# CI_V.net
KiCad netlist of a schematic drawn in EAGLE
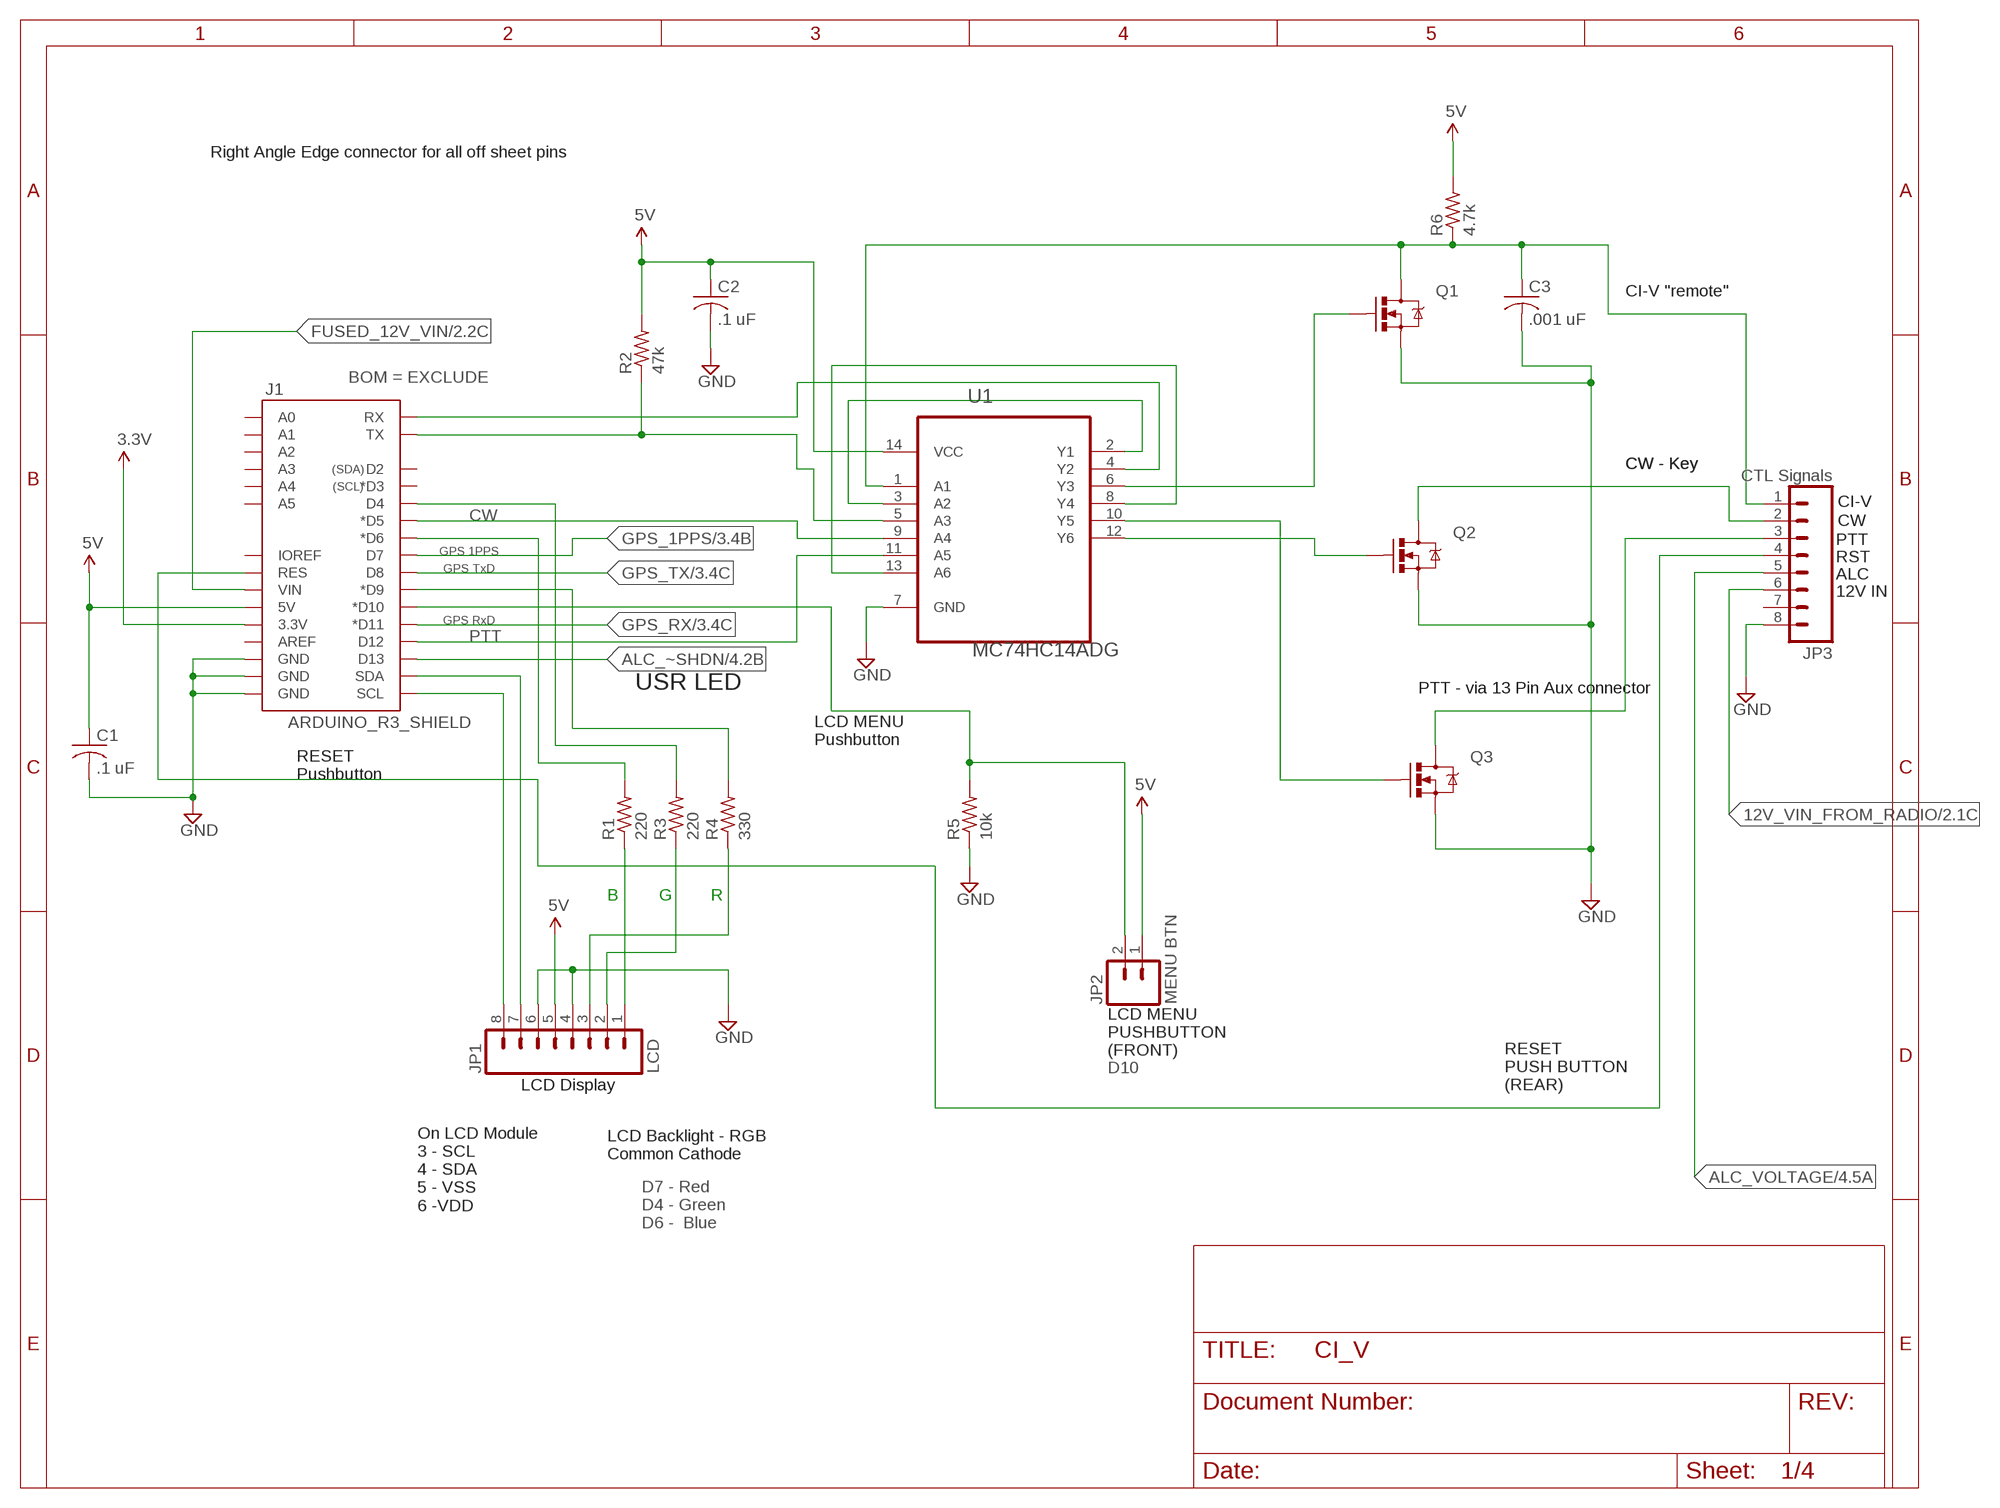
[diagram p0: schematic, sheet 1]
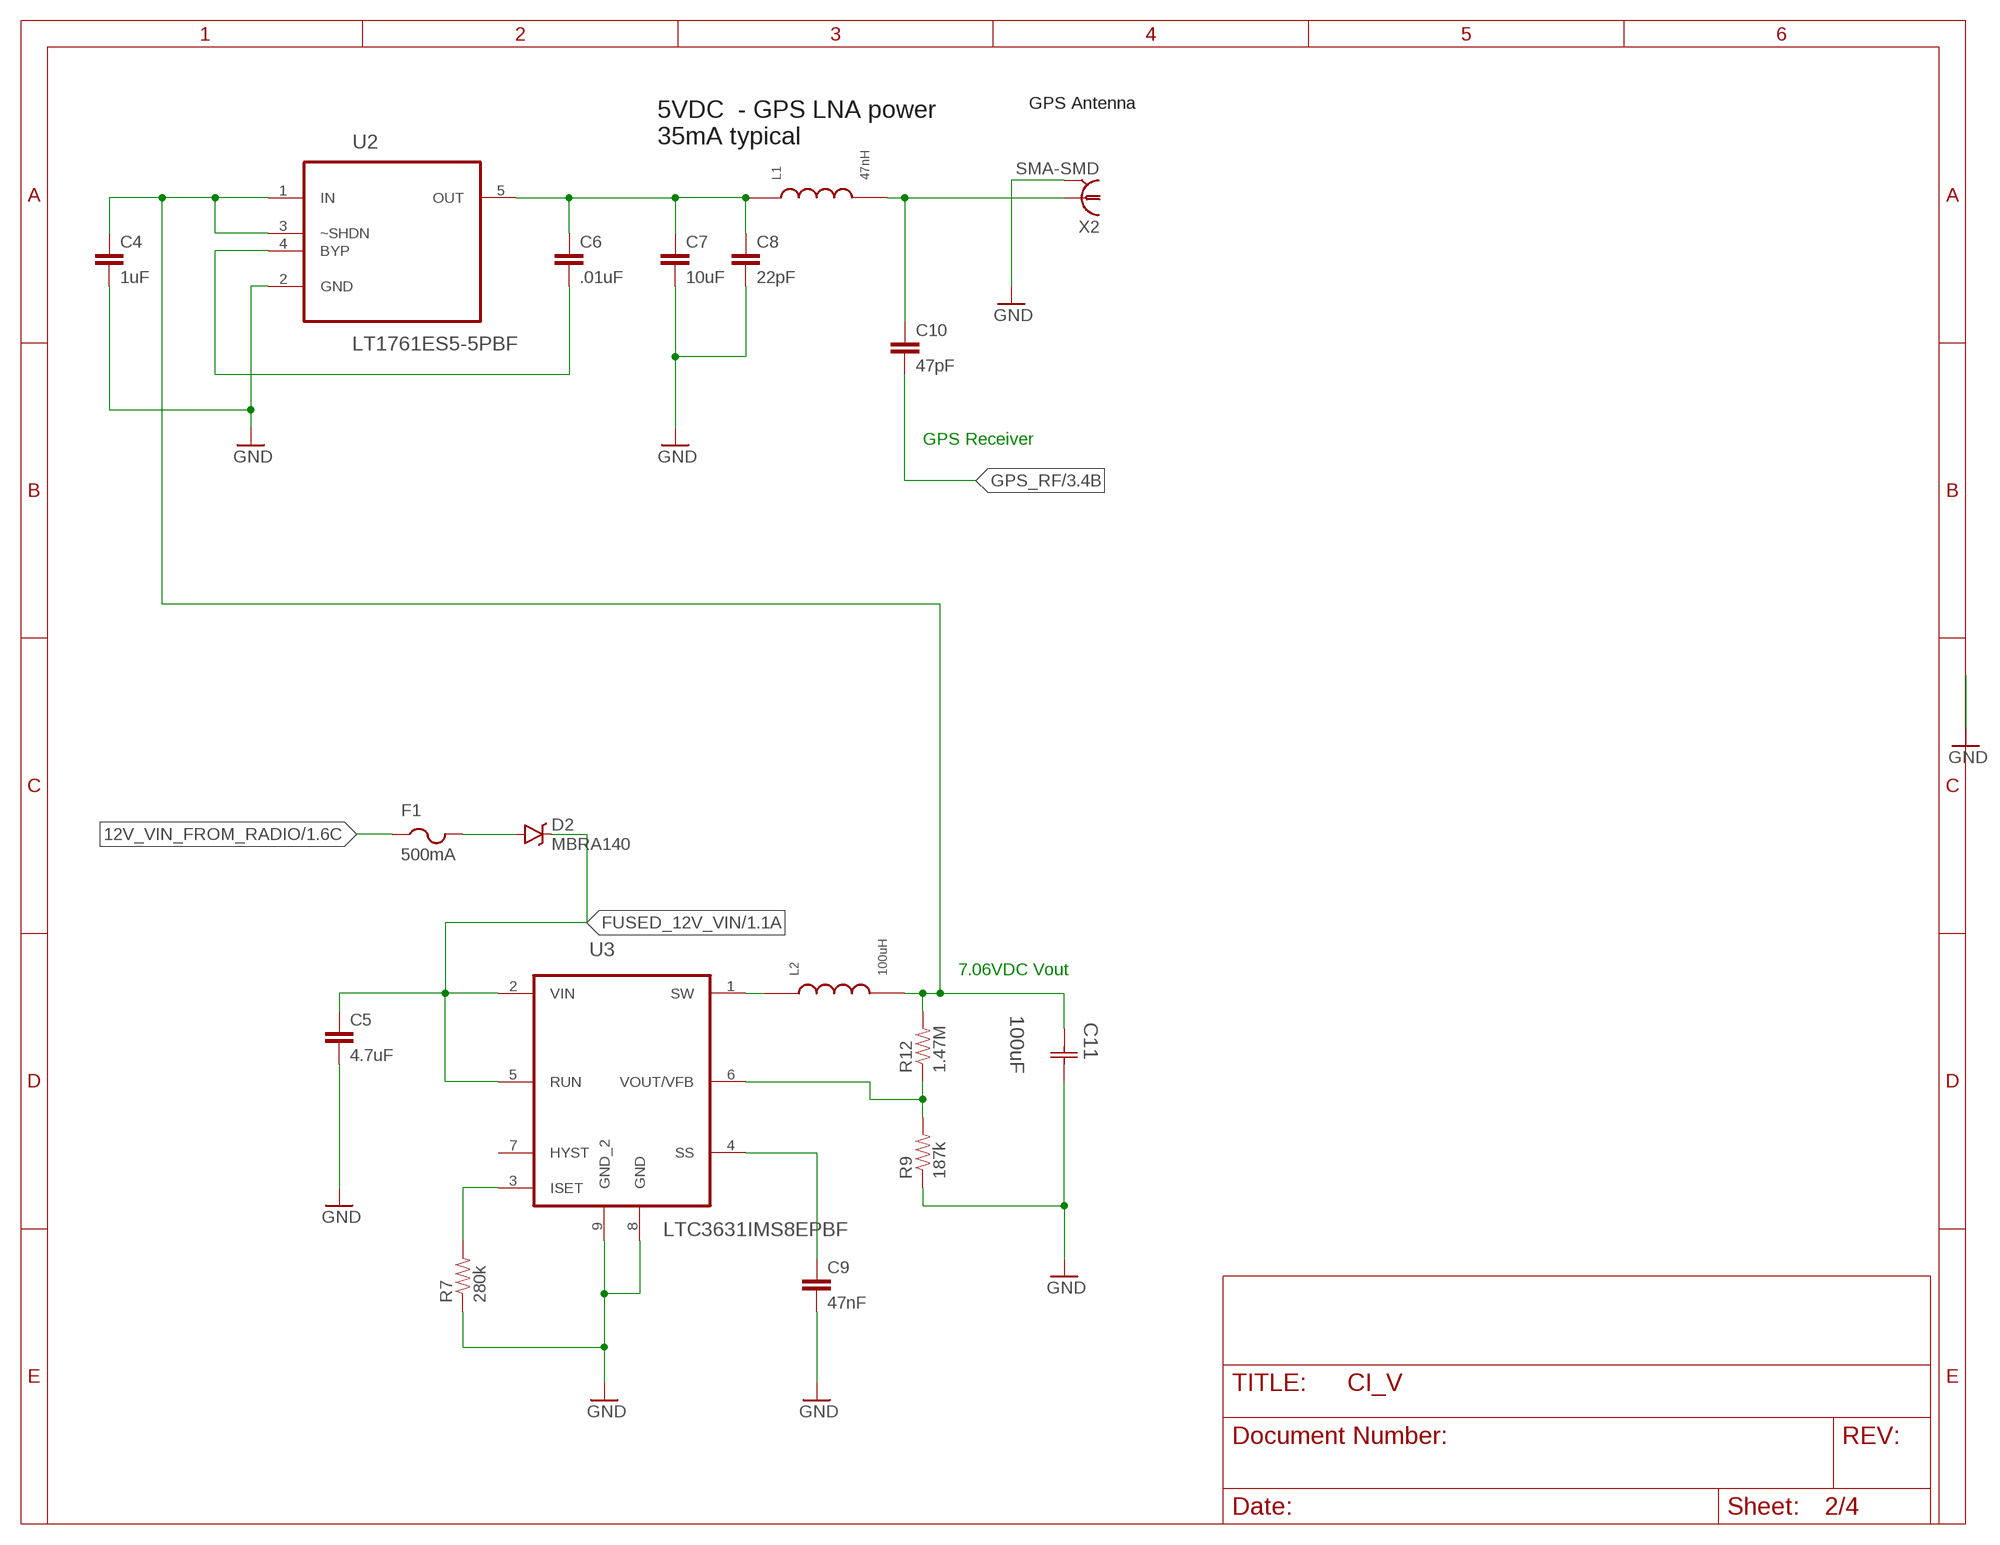
[diagram p1: schematic, sheet 2]
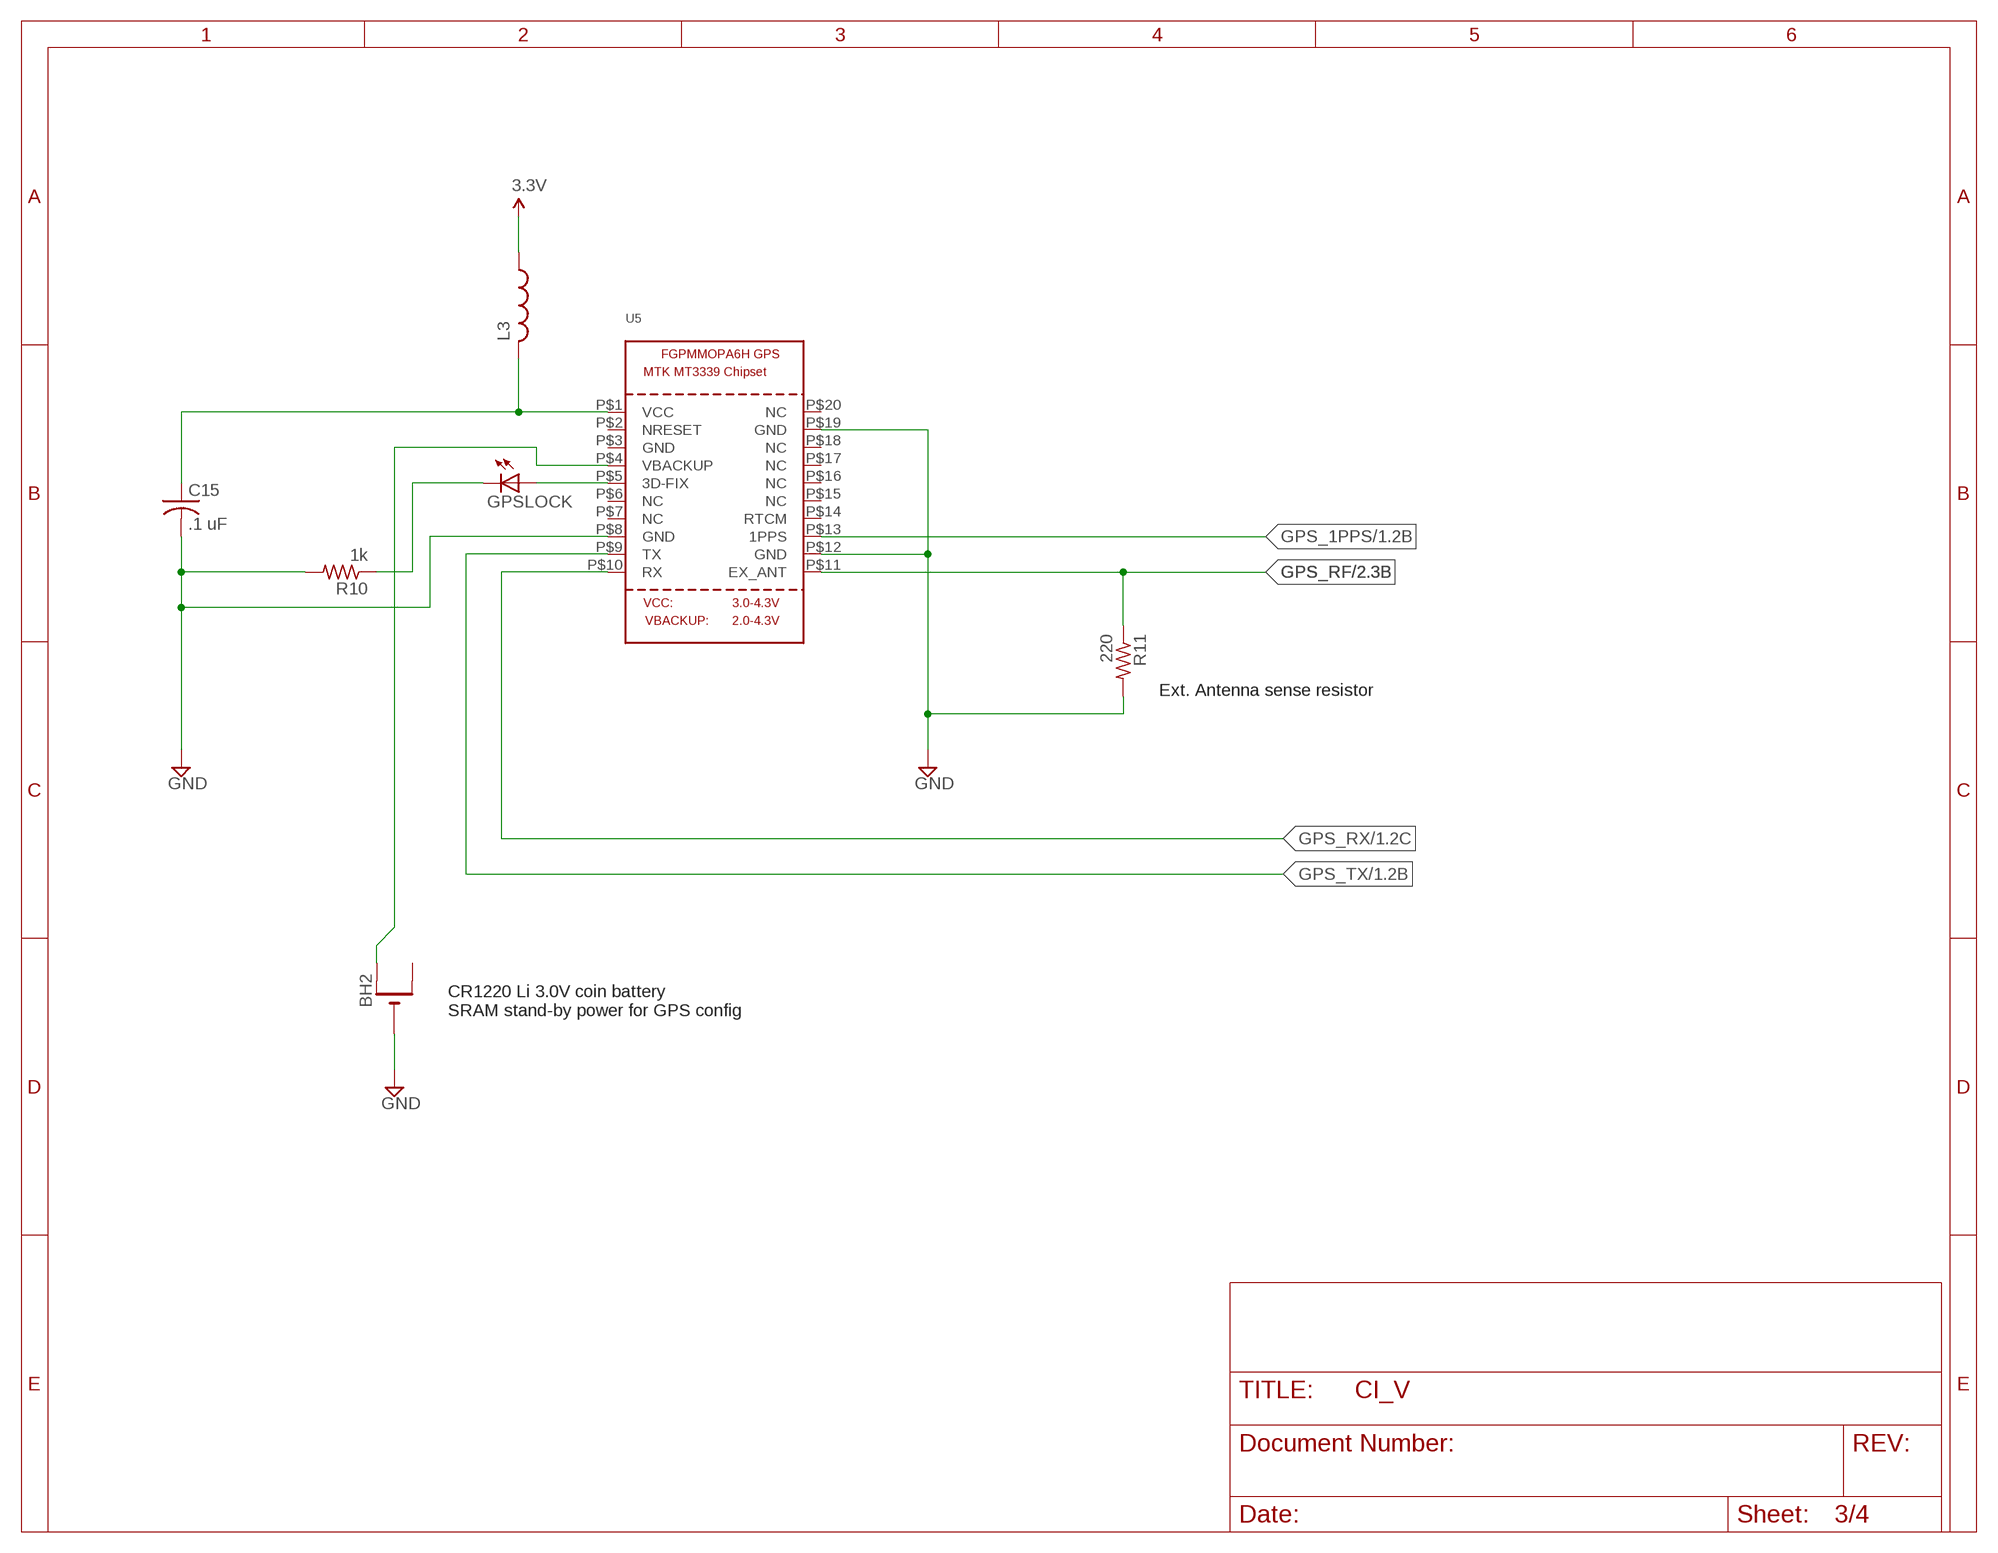
[diagram p2: schematic, sheet 3]
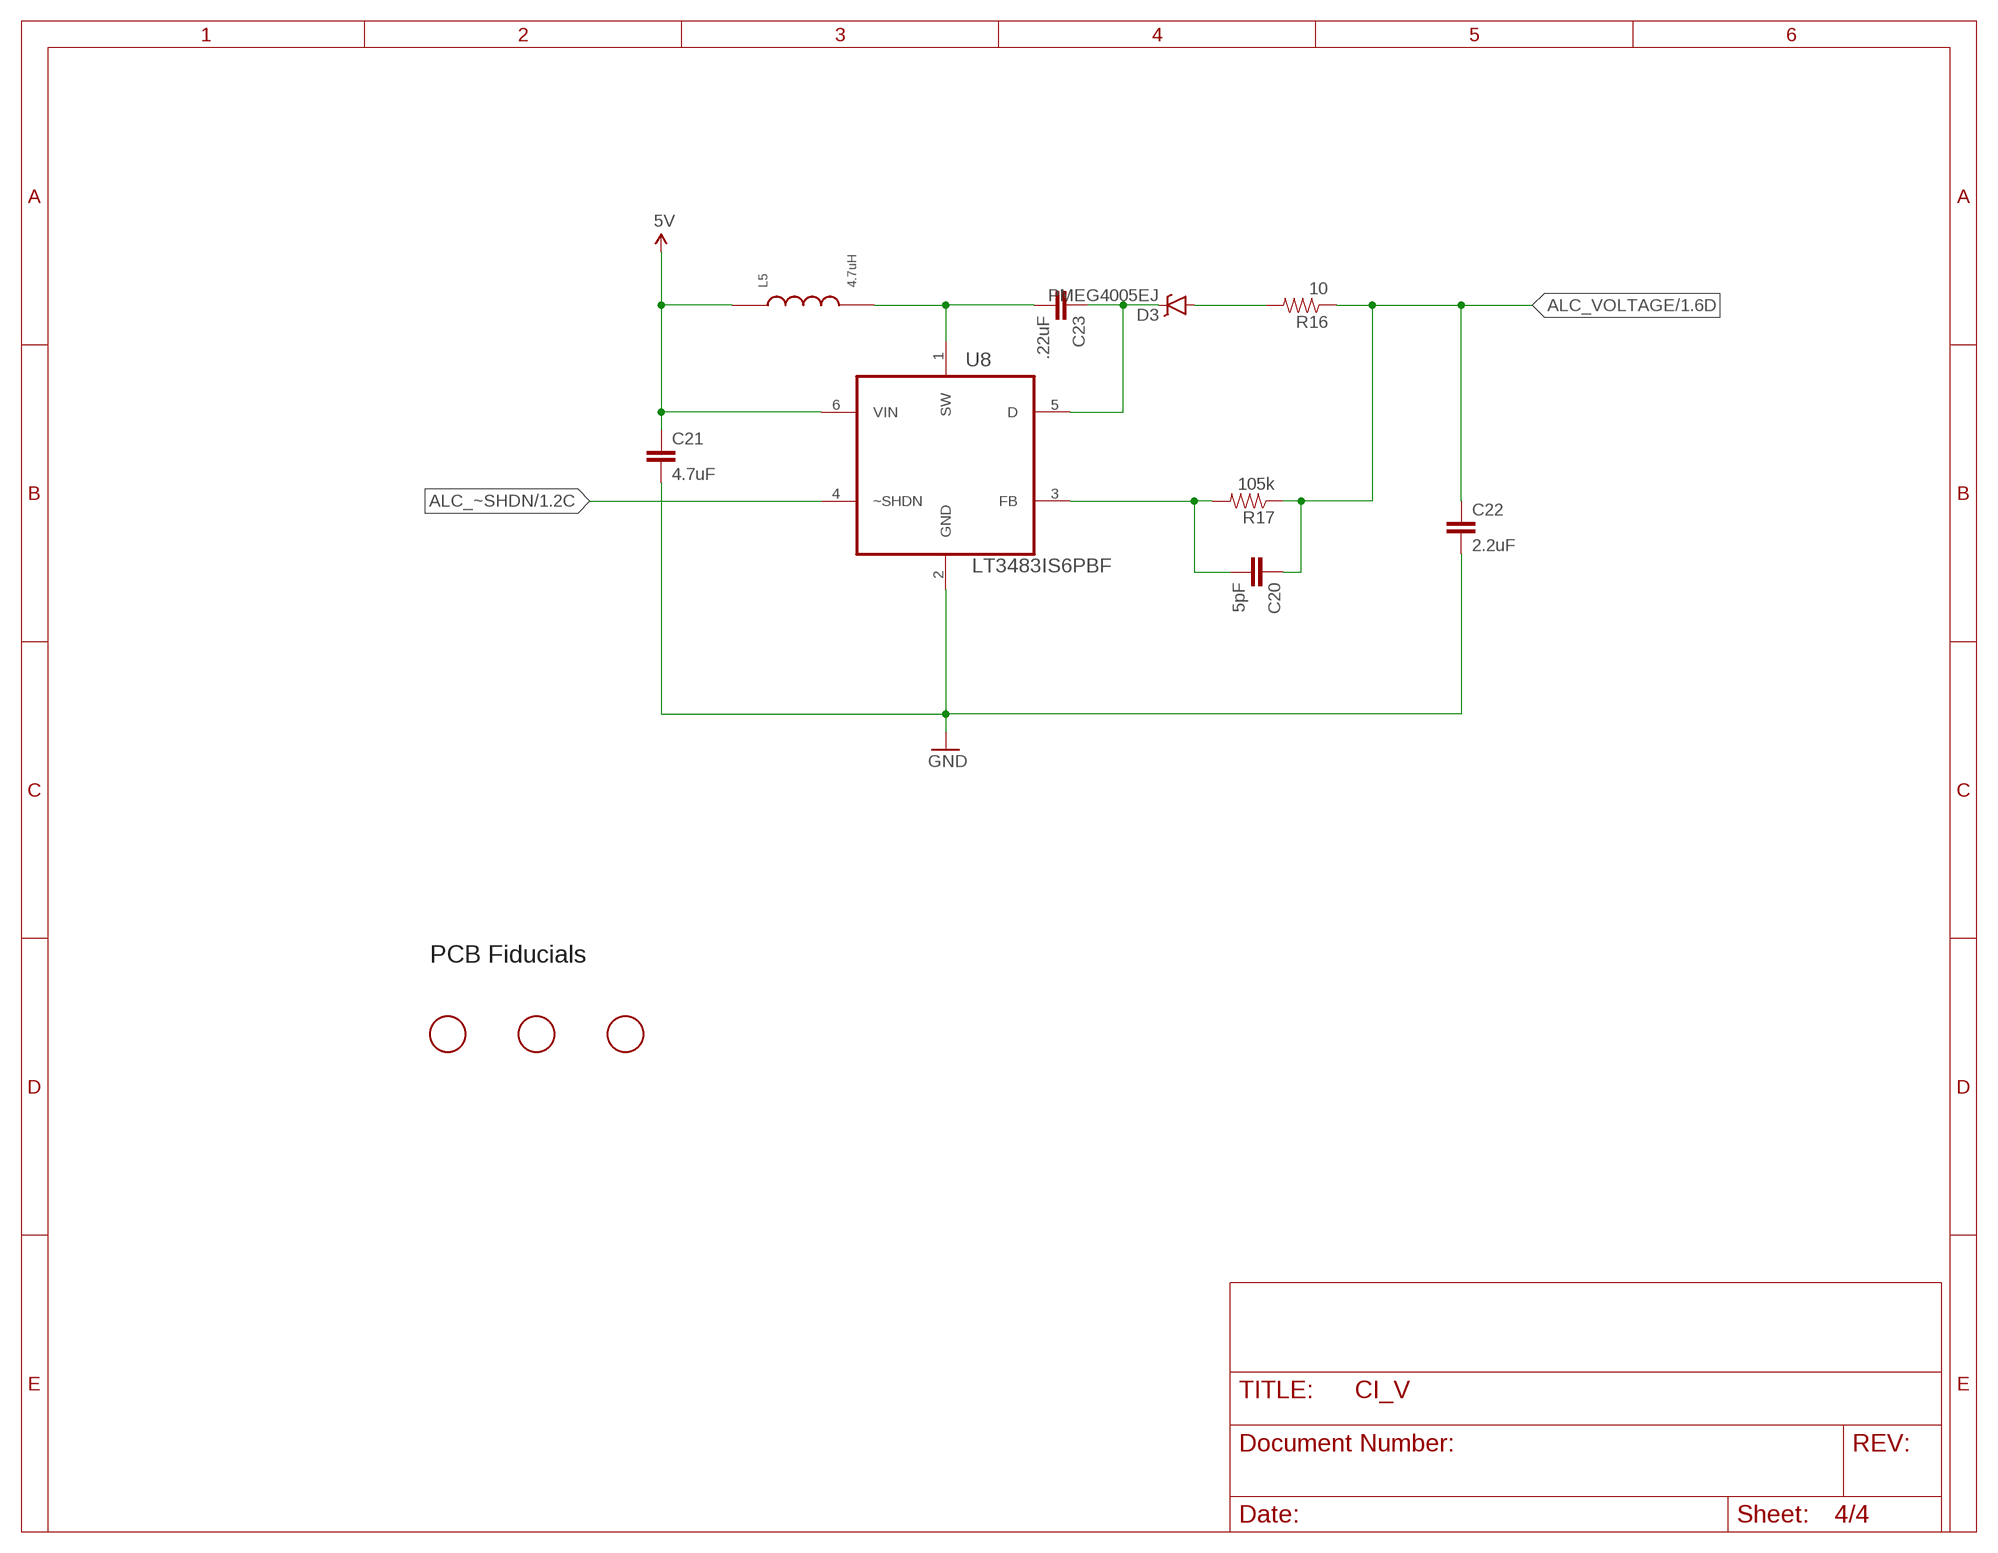
[diagram p3: schematic, sheet 4]

(export (version "E")
  (design (tool "Eeschema 10.0.6"))
  (components
    (comp (ref "C4")
      (value "1uF")
      (footprint "eagle-import:0805")
      (fields (field (name "PARTNO") "120-0001-015"))
      (libsource (lib "eagle-import") (part "CAP0805"))
    )
    (comp (ref "C5")
      (value "4.7uF")
      (footprint "eagle-import:1210")
      (fields (field (name "PARTNO") "120-0003-011"))
      (libsource (lib "eagle-import") (part "CAP1210"))
    )
    (comp (ref "C6")
      (value ".01uF")
      (footprint "eagle-import:0805")
      (fields (field (name "PARTNO") "120-0001-020"))
      (libsource (lib "eagle-import") (part "CAP0805"))
    )
    (comp (ref "C7")
      (value "10uF")
      (footprint "eagle-import:1210")
      (fields (field (name "PARTNO") "120-0003-010"))
      (libsource (lib "eagle-import") (part "CAP1210"))
    )
    (comp (ref "C8")
      (value "22pF")
      (footprint "eagle-import:0805")
      (fields (field (name "PARTNO") "120-0004-011"))
      (libsource (lib "eagle-import") (part "CAP0805"))
    )
    (comp (ref "C9")
      (value "47nF")
      (footprint "eagle-import:0805")
      (fields (field (name "PARTNO") "120-0001-013"))
      (libsource (lib "eagle-import") (part "CAP0805"))
    )
    (comp (ref "C10")
      (value "47pF")
      (footprint "eagle-import:0805")
      (fields (field (name "PARTNO") "120-0004-010"))
      (libsource (lib "eagle-import") (part "CAP0805"))
    )
    (comp (ref "C11")
      (value "100uF")
      (footprint "eagle-import:CAPCP6032X280N")
      (fields (field (name "MPN") "THJC226K016RJN") (field (name "PARTNO") "120-0005-050"))
      (libsource (lib "eagle-import") (part "THJC226K016RJN"))
    )
    (comp (ref "D2")
      (value "MBRA140")
      (footprint "eagle-import:SMA-DIODE")
      (fields (field (name "PARTNO") "140-0001-001"))
      (libsource (lib "eagle-import") (part "DIODE-SCHOTTKY-MBRA140"))
    )
    (comp (ref "F1")
      (value "500mA")
      (footprint "eagle-import:R1206")
      (fields (field (name "PARTNO") "145-0001-001"))
      (libsource (lib "eagle-import") (part "PTCFUSE-1206"))
    )
    (comp (ref "L1")
      (value "47nH")
      (footprint "eagle-import:0805")
      (fields (field (name "PARTNO") "155-0002-001"))
      (libsource (lib "eagle-import") (part "INDUCTORMURATA"))
    )
    (comp (ref "L2")
      (value "100uH")
      (footprint "eagle-import:SLF7045")
      (fields (field (name "PARTNO") "155-0001-001"))
      (libsource (lib "eagle-import") (part "INDUCTORTDKMURATA"))
    )
    (comp (ref "R7")
      (value "280k")
      (footprint "eagle-import:0805")
      (fields (field (name "PARTNO") "110-0002-015"))
      (libsource (lib "eagle-import") (part "RESISTOR0805-RES"))
    )
    (comp (ref "R9")
      (value "187k")
      (footprint "eagle-import:0805")
      (fields (field (name "PARTNO") "110-0002-020"))
      (libsource (lib "eagle-import") (part "RESISTOR0805-RES"))
    )
    (comp (ref "R12")
      (value "1.47M")
      (footprint "eagle-import:0805")
      (fields (field (name "PARTNO") "110-0002-010"))
      (libsource (lib "eagle-import") (part "RESISTOR0805-RES"))
    )
    (comp (ref "U2")
      (value "LT1761ES5-5PBF")
      (footprint "eagle-import:SOT95P280X100-5N")
      (fields (field (name "MPN") "LT1761ES5-5#PBF") (field (name "PARTNO") "230-0002-001"))
      (libsource (lib "eagle-import") (part "LT1761ES5-5PBF"))
    )
    (comp (ref "U3")
      (value "LTC3631IMS8EPBF")
      (footprint "eagle-import:SOP65P490X110-9N")
      (fields (field (name "MPN") "LTC3631IMS8E#PBF") (field (name "PARTNO") "230-0003-001"))
      (libsource (lib "eagle-import") (part "LTC3631IMS8EPBF"))
    )
    (comp (ref "X2")
      (value "SMA-SMD")
      (footprint "eagle-import:SMA-SMD")
      (fields (field (name "PARTNO") "125-0018-001"))
      (libsource (lib "eagle-import") (part "SMA-SMD"))
    )
    (comp (ref "C20")
      (value "5pF")
      (footprint "eagle-import:0805")
      (fields (field (name "PARTNO") "120-0004-010"))
      (libsource (lib "eagle-import") (part "CAP0805"))
    )
    (comp (ref "C21")
      (value "4.7uF")
      (footprint "eagle-import:1210")
      (fields (field (name "PARTNO") "120-0003-011"))
      (libsource (lib "eagle-import") (part "CAP1210"))
    )
    (comp (ref "C22")
      (value "2.2uF")
      (footprint "eagle-import:0805")
      (fields (field (name "PARTNO") "120-0002-011"))
      (libsource (lib "eagle-import") (part "CAP0805"))
    )
    (comp (ref "C23")
      (value ".22uF")
      (footprint "eagle-import:0805")
      (fields (field (name "PARTNO") "120-0001-022"))
      (libsource (lib "eagle-import") (part "CAP0805"))
    )
    (comp (ref "D3")
      (value "PMEG4005EJ")
      (footprint "eagle-import:SOD-323")
      (fields (field (name "PARTNO") "140-0002-001"))
      (libsource (lib "eagle-import") (part "DIODE-SCHOTTKY-PMEG4005EJ"))
    )
    (comp (ref "L5")
      (value "4.7uH")
      (footprint "eagle-import:0805")
      (fields (field (name "PARTNO") "155-0003-001"))
      (libsource (lib "eagle-import") (part "INDUCTORMURATA"))
    )
    (comp (ref "R16")
      (value "10")
      (footprint "eagle-import:0805")
      (fields (field (name "PARTNO") "110-0001-027"))
      (libsource (lib "eagle-import") (part "RESISTOR0805-RES"))
    )
    (comp (ref "R17")
      (value "105k")
      (footprint "eagle-import:0805")
      (fields (field (name "PARTNO") "110-0003-010"))
      (libsource (lib "eagle-import") (part "RESISTOR0805-RES"))
    )
    (comp (ref "U$1")
      (value "FIDUCIAL")
      (footprint "eagle-import:FIDUCIAL_1MM")
      (libsource (lib "eagle-import") (part "FIDUCIAL"))
    )
    (comp (ref "U$6")
      (value "FIDUCIAL")
      (footprint "eagle-import:FIDUCIAL_1MM")
      (libsource (lib "eagle-import") (part "FIDUCIAL"))
    )
    (comp (ref "U$7")
      (value "FIDUCIAL")
      (footprint "eagle-import:FIDUCIAL_1MM")
      (libsource (lib "eagle-import") (part "FIDUCIAL"))
    )
    (comp (ref "U8")
      (value "LT3483IS6PBF")
      (footprint "eagle-import:SOT95P280X100-6N")
      (fields (field (name "MPN") "LT3483IS6#PBF"))
      (libsource (lib "eagle-import") (part "LT3483IS6PBF"))
    )
    (comp (ref "C1")
      (value ".1 uF")
      (footprint "eagle-import:C0805")
      (fields (field (name "PARTNO") "120-0001-010"))
      (libsource (lib "eagle-import") (part "C-USC0805"))
    )
    (comp (ref "C2")
      (value ".1 uF")
      (footprint "eagle-import:C0805")
      (fields (field (name "PARTNO") "120-0001-010"))
      (libsource (lib "eagle-import") (part "C-USC0805"))
    )
    (comp (ref "C3")
      (value ".001 uF")
      (footprint "eagle-import:C0805")
      (fields (field (name "PARTNO") "120-0001-015"))
      (libsource (lib "eagle-import") (part "C-USC0805"))
    )
    (comp (ref "J1")
      (value "ARDUINO_R3_SHIELD")
      (footprint "eagle-import:UNO_R3_SHIELD")
      (fields (field (name "BOM") "EXCLUDE"))
      (libsource (lib "eagle-import") (part "ARDUINO_R3_SHIELD"))
    )
    (comp (ref "JP1")
      (value "LCD")
      (footprint "eagle-import:1X08_PIN1_NO_SILK")
      (fields (field (name "PARTNO") "125-0019-001"))
      (libsource (lib "eagle-import") (part "M08NO_SILK"))
    )
    (comp (ref "JP2")
      (value "MENU BTN")
      (footprint "eagle-import:1X02")
      (fields (field (name "PARTNO") "125-0019-001"))
      (libsource (lib "eagle-import") (part "M02PTH"))
    )
    (comp (ref "JP3")
      (value "CTL Signals")
      (footprint "eagle-import:1X08_PIN1_NO_SILK")
      (fields (field (name "PARTNO") "125-0019-001"))
      (libsource (lib "eagle-import") (part "M08NO_SILK"))
    )
    (comp (ref "Q1")
      (value "MOSFET-NCHANNELBSS123LT1G")
      (footprint "eagle-import:SOT23-3")
      (fields (field (name "PARTNO") "185-0001-001"))
      (libsource (lib "eagle-import") (part "MOSFET-NCHANNELBSS123LT1G"))
    )
    (comp (ref "Q2")
      (value "MOSFET-NCHANNELBSS123LT1G")
      (footprint "eagle-import:SOT23-3")
      (fields (field (name "PARTNO") "185-0001-001"))
      (libsource (lib "eagle-import") (part "MOSFET-NCHANNELBSS123LT1G"))
    )
    (comp (ref "Q3")
      (value "MOSFET-NCHANNELBSS123LT1G")
      (footprint "eagle-import:SOT23-3")
      (fields (field (name "PARTNO") "185-0001-001"))
      (libsource (lib "eagle-import") (part "MOSFET-NCHANNELBSS123LT1G"))
    )
    (comp (ref "R1")
      (value "220")
      (footprint "eagle-import:R0805")
      (fields (field (name "PARTNO") "110-0001-010"))
      (libsource (lib "eagle-import") (part "R-US_R0805"))
    )
    (comp (ref "R2")
      (value "47k")
      (footprint "eagle-import:R0805")
      (fields (field (name "PARTNO") "110-0001-030"))
      (libsource (lib "eagle-import") (part "R-US_R0805"))
    )
    (comp (ref "R3")
      (value "220")
      (footprint "eagle-import:R0805")
      (fields (field (name "PARTNO") "110-0001-010"))
      (libsource (lib "eagle-import") (part "R-US_R0805"))
    )
    (comp (ref "R4")
      (value "330")
      (footprint "eagle-import:R0805")
      (fields (field (name "PARTNO") "110-0001-025"))
      (libsource (lib "eagle-import") (part "R-US_R0805"))
    )
    (comp (ref "R5")
      (value "10k")
      (footprint "eagle-import:R0805")
      (fields (field (name "PARTNO") "110-0001-025"))
      (libsource (lib "eagle-import") (part "R-US_R0805"))
    )
    (comp (ref "R6")
      (value "4.7k")
      (footprint "eagle-import:R0805")
      (fields (field (name "PARTNO") "110-0001-030"))
      (libsource (lib "eagle-import") (part "R-US_R0805"))
    )
    (comp (ref "U1")
      (value "MC74HC14ADG")
      (footprint "eagle-import:SOIC127P600X175-14N")
      (fields (field (name "PARTNO") "200-0001-001"))
      (libsource (lib "eagle-import") (part "MC74HC14ADG"))
    )
    (comp (ref "BH2")
      (value "CR1220SMT")
      (footprint "eagle-import:CR1220-SMD")
      (fields (field (name "PARTNO") "165-0001-001"))
      (libsource (lib "eagle-import") (part "CR1220SMT"))
    )
    (comp (ref "C15")
      (value ".1 uF")
      (footprint "eagle-import:C0805")
      (fields (field (name "PARTNO") "120-0001-010"))
      (libsource (lib "eagle-import") (part "C-USC0805"))
    )
    (comp (ref "GPSLOCK")
      (value "LEDCHIPLED_0805")
      (footprint "eagle-import:CHIPLED_0805")
      (fields (field (name "PARTNO") "160-0007-001"))
      (libsource (lib "eagle-import") (part "LEDCHIPLED_0805"))
    )
    (comp (ref "L3")
      (value "L-USL2012C")
      (footprint "eagle-import:L2012C")
      (fields (field (name "PARTNO") "155-0004-001"))
      (libsource (lib "eagle-import") (part "L-USL2012C"))
    )
    (comp (ref "R10")
      (value "1k")
      (footprint "eagle-import:R0805")
      (fields (field (name "PARTNO") "110-0001-029"))
      (libsource (lib "eagle-import") (part "R-US_R0805"))
    )
    (comp (ref "R11")
      (value "220")
      (footprint "eagle-import:R0805")
      (fields (field (name "PARTNO") "110-0001-010"))
      (libsource (lib "eagle-import") (part "R-US_R0805"))
    )
    (comp (ref "U5")
      (value "GPS_FGPMMOPA6H")
      (footprint "eagle-import:FGPMMOPA6H")
      (fields (field (name "PARTNO") "240-0001-001"))
      (libsource (lib "eagle-import") (part "GPS_FGPMMOPA6H"))
    )
  )
  (nets
    (net (code "1") (name "3.3V") (class "Default")
      (node (ref "J1") (pin "3.3V") (pinfunction "3.3V_3.3V") (pintype "bidirectional"))
      (node (ref "L3") (pin "1") (pinfunction "1_1") (pintype "passive"))
    )
    (net (code "2") (name "5V") (class "Default")
      (node (ref "C1") (pin "1") (pinfunction "1_1") (pintype "passive"))
      (node (ref "C2") (pin "1") (pinfunction "1_1") (pintype "passive"))
      (node (ref "C21") (pin "1") (pinfunction "1_1") (pintype "passive"))
      (node (ref "J1") (pin "5V") (pinfunction "5V_5V") (pintype "bidirectional"))
      (node (ref "JP1") (pin "5") (pinfunction "5_5") (pintype "passive"))
      (node (ref "JP2") (pin "1") (pinfunction "1_1") (pintype "passive"))
      (node (ref "L5") (pin "1") (pinfunction "1_1") (pintype "passive"))
      (node (ref "R2") (pin "2") (pinfunction "2_2") (pintype "passive"))
      (node (ref "R6") (pin "2") (pinfunction "2_2") (pintype "passive"))
      (node (ref "U1") (pin "14") (pinfunction "VCC_14") (pintype "power_in"))
      (node (ref "U8") (pin "6") (pinfunction "VIN_6") (pintype "power_in"))
    )
    (net (code "3") (name "12V_VIN_FROM_RADIO") (class "Default")
      (node (ref "F1") (pin "1") (pinfunction "1_1") (pintype "passive"))
      (node (ref "JP3") (pin "6") (pinfunction "6_6") (pintype "passive"))
    )
    (net (code "4") (name "ALC_VOLTAGE") (class "Default")
      (node (ref "C20") (pin "1") (pinfunction "1_1") (pintype "passive"))
      (node (ref "C22") (pin "1") (pinfunction "1_1") (pintype "passive"))
      (node (ref "JP3") (pin "5") (pinfunction "5_5") (pintype "passive"))
      (node (ref "R16") (pin "1") (pinfunction "1_1") (pintype "passive"))
      (node (ref "R17") (pin "1") (pinfunction "1_1") (pintype "passive"))
    )
    (net (code "5") (name "ALC_~{SHDN}") (class "Default")
      (node (ref "J1") (pin "D13") (pinfunction "D13_D13") (pintype "bidirectional"))
      (node (ref "U8") (pin "4") (pinfunction "~{SHDN}_4") (pintype "input"))
    )
    (net (code "6") (name "CW") (class "Default")
      (node (ref "J1") (pin "D5") (pinfunction "*D5_D5") (pintype "bidirectional"))
      (node (ref "U1") (pin "9") (pinfunction "A4_9") (pintype "input"))
    )
    (net (code "7") (name "FUSED_12V_VIN") (class "Default")
      (node (ref "C5") (pin "1") (pinfunction "1_1") (pintype "passive"))
      (node (ref "D2") (pin "C") (pinfunction "C_C") (pintype "passive"))
      (node (ref "J1") (pin "VIN") (pinfunction "VIN_VIN") (pintype "bidirectional"))
      (node (ref "U3") (pin "2") (pinfunction "VIN_2") (pintype "power_in"))
      (node (ref "U3") (pin "5") (pinfunction "RUN_5") (pintype "input"))
    )
    (net (code "8") (name "GND") (class "Default")
      (node (ref "BH2") (pin "-") (pinfunction "-_-") (pintype "passive"))
      (node (ref "C1") (pin "2") (pinfunction "2_2") (pintype "passive"))
      (node (ref "C11") (pin "2") (pinfunction "C2_2") (pintype "passive"))
      (node (ref "C15") (pin "2") (pinfunction "2_2") (pintype "passive"))
      (node (ref "C2") (pin "2") (pinfunction "2_2") (pintype "passive"))
      (node (ref "C21") (pin "2") (pinfunction "2_2") (pintype "passive"))
      (node (ref "C22") (pin "2") (pinfunction "2_2") (pintype "passive"))
      (node (ref "C3") (pin "2") (pinfunction "2_2") (pintype "passive"))
      (node (ref "C4") (pin "2") (pinfunction "2_2") (pintype "passive"))
      (node (ref "C5") (pin "2") (pinfunction "2_2") (pintype "passive"))
      (node (ref "C7") (pin "2") (pinfunction "2_2") (pintype "passive"))
      (node (ref "C8") (pin "2") (pinfunction "2_2") (pintype "passive"))
      (node (ref "C9") (pin "2") (pinfunction "2_2") (pintype "passive"))
      (node (ref "J1") (pin "GND@0") (pinfunction "GND_GND@0") (pintype "bidirectional"))
      (node (ref "J1") (pin "GND@1") (pinfunction "GND_GND@1") (pintype "bidirectional"))
      (node (ref "J1") (pin "GND@2") (pinfunction "GND_GND@2") (pintype "bidirectional"))
      (node (ref "JP1") (pin "4") (pinfunction "4_4") (pintype "passive"))
      (node (ref "JP1") (pin "6") (pinfunction "6_6") (pintype "passive"))
      (node (ref "JP3") (pin "8") (pinfunction "8_8") (pintype "passive"))
      (node (ref "Q1") (pin "2") (pinfunction "S_2") (pintype "passive"))
      (node (ref "Q2") (pin "2") (pinfunction "S_2") (pintype "passive"))
      (node (ref "Q3") (pin "2") (pinfunction "S_2") (pintype "passive"))
      (node (ref "R10") (pin "2") (pinfunction "2_2") (pintype "passive"))
      (node (ref "R11") (pin "2") (pinfunction "2_2") (pintype "passive"))
      (node (ref "R5") (pin "1") (pinfunction "1_1") (pintype "passive"))
      (node (ref "R7") (pin "1") (pinfunction "1_1") (pintype "passive"))
      (node (ref "R9") (pin "1") (pinfunction "1_1") (pintype "passive"))
      (node (ref "U1") (pin "7") (pinfunction "GND_7") (pintype "passive"))
      (node (ref "U2") (pin "2") (pinfunction "GND_2") (pintype "passive"))
      (node (ref "U3") (pin "8") (pinfunction "GND_8") (pintype "passive"))
      (node (ref "U3") (pin "9") (pinfunction "GND_2_9") (pintype "passive"))
      (node (ref "U5") (pin "P$12") (pinfunction "GND_P$12") (pintype "bidirectional"))
      (node (ref "U5") (pin "P$19") (pinfunction "GND_P$19") (pintype "bidirectional"))
      (node (ref "U5") (pin "P$8") (pinfunction "GND_P$8") (pintype "bidirectional"))
      (node (ref "U8") (pin "2") (pinfunction "GND_2") (pintype "passive"))
      (node (ref "X2") (pin "2@1") (pinfunction "2_2@1") (pintype "passive"))
      (node (ref "X2") (pin "2@2") (pinfunction "2_2@2") (pintype "passive"))
      (node (ref "X2") (pin "2@3") (pinfunction "2_2@3") (pintype "passive"))
      (node (ref "X2") (pin "2@4") (pinfunction "2_2@4") (pintype "passive"))
      (node (ref "X2") (pin "2@5") (pinfunction "2_2@5") (pintype "passive"))
      (node (ref "X2") (pin "2@6") (pinfunction "2_2@6") (pintype "passive"))
    )
    (net (code "9") (name "GPS_1PPS") (class "Default")
      (node (ref "J1") (pin "D7") (pinfunction "D7_D7") (pintype "bidirectional"))
      (node (ref "U5") (pin "P$13") (pinfunction "1PPS_P$13") (pintype "bidirectional"))
    )
    (net (code "10") (name "GPS_RF") (class "Default")
      (node (ref "C10") (pin "2") (pinfunction "2_2") (pintype "passive"))
      (node (ref "R11") (pin "1") (pinfunction "1_1") (pintype "passive"))
      (node (ref "U5") (pin "P$11") (pinfunction "EX_ANT_P$11") (pintype "bidirectional"))
    )
    (net (code "11") (name "GPS_RX") (class "Default")
      (node (ref "J1") (pin "D11") (pinfunction "*D11_D11") (pintype "bidirectional"))
      (node (ref "U5") (pin "P$10") (pinfunction "RX_P$10") (pintype "bidirectional"))
    )
    (net (code "12") (name "GPS_TX") (class "Default")
      (node (ref "J1") (pin "D8") (pinfunction "D8_D8") (pintype "bidirectional"))
      (node (ref "U5") (pin "P$9") (pinfunction "TX_P$9") (pintype "bidirectional"))
    )
    (net (code "13") (name "Net-(BH2-+)") (class "Default")
      (node (ref "BH2") (pin "+$1") (pinfunction "+_+$1") (pintype "passive"))
      (node (ref "U5") (pin "P$4") (pinfunction "VBACKUP_P$4") (pintype "bidirectional"))
    )
    (net (code "14") (name "Net-(C10-Pad1)") (class "Default")
      (node (ref "C10") (pin "1") (pinfunction "1_1") (pintype "passive"))
      (node (ref "L1") (pin "2") (pinfunction "2_2") (pintype "passive"))
      (node (ref "X2") (pin "1") (pinfunction "1_1") (pintype "passive"))
    )
    (net (code "15") (name "Net-(C11-C1)") (class "Default")
      (node (ref "C11") (pin "1") (pinfunction "C1_1") (pintype "passive"))
      (node (ref "C4") (pin "1") (pinfunction "1_1") (pintype "passive"))
      (node (ref "L2") (pin "2") (pinfunction "2_2") (pintype "passive"))
      (node (ref "R12") (pin "2") (pinfunction "2_2") (pintype "passive"))
      (node (ref "U2") (pin "1") (pinfunction "IN_1") (pintype "input"))
      (node (ref "U2") (pin "3") (pinfunction "~{SHDN}_3") (pintype "input"))
    )
    (net (code "16") (name "Net-(D2-PadA)") (class "Default")
      (node (ref "D2") (pin "A") (pinfunction "A_A") (pintype "passive"))
      (node (ref "F1") (pin "2") (pinfunction "2_2") (pintype "passive"))
    )
    (net (code "17") (name "Net-(D3-PadA)") (class "Default")
      (node (ref "D3") (pin "A") (pinfunction "A_A") (pintype "passive"))
      (node (ref "R16") (pin "2") (pinfunction "2_2") (pintype "passive"))
    )
    (net (code "18") (name "Net-(GPSLOCK-PadC)") (class "Default")
      (node (ref "GPSLOCK") (pin "C") (pinfunction "C_C") (pintype "passive"))
      (node (ref "R10") (pin "1") (pinfunction "1_1") (pintype "passive"))
    )
    (net (code "19") (name "Net-(J1-*D6)") (class "Default")
      (node (ref "J1") (pin "D6") (pinfunction "*D6_D6") (pintype "bidirectional"))
      (node (ref "R1") (pin "2") (pinfunction "2_2") (pintype "passive"))
    )
    (net (code "20") (name "Net-(J1-*D9)") (class "Default")
      (node (ref "J1") (pin "D9") (pinfunction "*D9_D9") (pintype "bidirectional"))
      (node (ref "R4") (pin "2") (pinfunction "2_2") (pintype "passive"))
    )
    (net (code "21") (name "Net-(J1-*D10)") (class "Default")
      (node (ref "J1") (pin "D10") (pinfunction "*D10_D10") (pintype "bidirectional"))
      (node (ref "JP2") (pin "2") (pinfunction "2_2") (pintype "passive"))
      (node (ref "R5") (pin "2") (pinfunction "2_2") (pintype "passive"))
    )
    (net (code "22") (name "Net-(J1-PadD4)") (class "Default")
      (node (ref "J1") (pin "D4") (pinfunction "D4_D4") (pintype "bidirectional"))
      (node (ref "R3") (pin "2") (pinfunction "2_2") (pintype "passive"))
    )
    (net (code "23") (name "Net-(J1-PadRES)") (class "Default")
      (node (ref "J1") (pin "RES") (pinfunction "RES_RES") (pintype "bidirectional"))
      (node (ref "JP3") (pin "4") (pinfunction "4_4") (pintype "passive"))
    )
    (net (code "24") (name "Net-(J1-PadSCL)") (class "Default")
      (node (ref "J1") (pin "SCL") (pinfunction "SCL_SCL") (pintype "bidirectional"))
      (node (ref "JP1") (pin "8") (pinfunction "8_8") (pintype "passive"))
    )
    (net (code "25") (name "Net-(J1-PadSDA)") (class "Default")
      (node (ref "J1") (pin "SDA") (pinfunction "SDA_SDA") (pintype "bidirectional"))
      (node (ref "JP1") (pin "7") (pinfunction "7_7") (pintype "passive"))
    )
    (net (code "26") (name "Net-(JP1-Pad1)") (class "Default")
      (node (ref "JP1") (pin "1") (pinfunction "1_1") (pintype "passive"))
      (node (ref "R1") (pin "1") (pinfunction "1_1") (pintype "passive"))
    )
    (net (code "27") (name "Net-(JP1-Pad2)") (class "Default")
      (node (ref "JP1") (pin "2") (pinfunction "2_2") (pintype "passive"))
      (node (ref "R3") (pin "1") (pinfunction "1_1") (pintype "passive"))
    )
    (net (code "28") (name "Net-(JP1-Pad3)") (class "Default")
      (node (ref "JP1") (pin "3") (pinfunction "3_3") (pintype "passive"))
      (node (ref "R4") (pin "1") (pinfunction "1_1") (pintype "passive"))
    )
    (net (code "29") (name "Net-(Q1-D)") (class "Default")
      (node (ref "C3") (pin "1") (pinfunction "1_1") (pintype "passive"))
      (node (ref "JP3") (pin "1") (pinfunction "1_1") (pintype "passive"))
      (node (ref "Q1") (pin "3") (pinfunction "D_3") (pintype "passive"))
      (node (ref "R6") (pin "1") (pinfunction "1_1") (pintype "passive"))
      (node (ref "U1") (pin "1") (pinfunction "A1_1") (pintype "input"))
    )
    (net (code "30") (name "Net-(Q1-G)") (class "Default")
      (node (ref "Q1") (pin "1") (pinfunction "G_1") (pintype "passive"))
      (node (ref "U1") (pin "6") (pinfunction "Y3_6") (pintype "output"))
    )
    (net (code "31") (name "Net-(Q2-D)") (class "Default")
      (node (ref "JP3") (pin "2") (pinfunction "2_2") (pintype "passive"))
      (node (ref "Q2") (pin "3") (pinfunction "D_3") (pintype "passive"))
    )
    (net (code "32") (name "Net-(Q2-G)") (class "Default")
      (node (ref "Q2") (pin "1") (pinfunction "G_1") (pintype "passive"))
      (node (ref "U1") (pin "12") (pinfunction "Y6_12") (pintype "output"))
    )
    (net (code "33") (name "Net-(Q3-D)") (class "Default")
      (node (ref "JP3") (pin "3") (pinfunction "3_3") (pintype "passive"))
      (node (ref "Q3") (pin "3") (pinfunction "D_3") (pintype "passive"))
    )
    (net (code "34") (name "Net-(Q3-G)") (class "Default")
      (node (ref "Q3") (pin "1") (pinfunction "G_1") (pintype "passive"))
      (node (ref "U1") (pin "10") (pinfunction "Y5_10") (pintype "output"))
    )
    (net (code "35") (name "Net-(U1-A2)") (class "Default")
      (node (ref "U1") (pin "2") (pinfunction "Y1_2") (pintype "output"))
      (node (ref "U1") (pin "3") (pinfunction "A2_3") (pintype "input"))
    )
    (net (code "36") (name "Net-(U1-A3)") (class "Default")
      (node (ref "J1") (pin "TX") (pinfunction "TX_TX") (pintype "bidirectional"))
      (node (ref "R2") (pin "1") (pinfunction "1_1") (pintype "passive"))
      (node (ref "U1") (pin "5") (pinfunction "A3_5") (pintype "input"))
    )
    (net (code "37") (name "Net-(U1-A6)") (class "Default")
      (node (ref "U1") (pin "13") (pinfunction "A6_13") (pintype "input"))
      (node (ref "U1") (pin "8") (pinfunction "Y4_8") (pintype "output"))
    )
    (net (code "38") (name "Net-(U1-Y2)") (class "Default")
      (node (ref "J1") (pin "RX") (pinfunction "RX_RX") (pintype "bidirectional"))
      (node (ref "U1") (pin "4") (pinfunction "Y2_4") (pintype "output"))
    )
    (net (code "39") (name "Net-(U2-BYP)") (class "Default")
      (node (ref "C6") (pin "2") (pinfunction "2_2") (pintype "passive"))
      (node (ref "U2") (pin "4") (pinfunction "BYP_4") (pintype "passive"))
    )
    (net (code "40") (name "Net-(U2-OUT)") (class "Default")
      (node (ref "C6") (pin "1") (pinfunction "1_1") (pintype "passive"))
      (node (ref "C7") (pin "1") (pinfunction "1_1") (pintype "passive"))
      (node (ref "C8") (pin "1") (pinfunction "1_1") (pintype "passive"))
      (node (ref "L1") (pin "1") (pinfunction "1_1") (pintype "passive"))
      (node (ref "U2") (pin "5") (pinfunction "OUT_5") (pintype "output"))
    )
    (net (code "41") (name "Net-(U3-ISET)") (class "Default")
      (node (ref "R7") (pin "2") (pinfunction "2_2") (pintype "passive"))
      (node (ref "U3") (pin "3") (pinfunction "ISET_3") (pintype "input"))
    )
    (net (code "42") (name "Net-(U3-SS)") (class "Default")
      (node (ref "C9") (pin "1") (pinfunction "1_1") (pintype "passive"))
      (node (ref "U3") (pin "4") (pinfunction "SS_4") (pintype "input"))
    )
    (net (code "43") (name "Net-(U3-SW)") (class "Default")
      (node (ref "L2") (pin "1") (pinfunction "1_1") (pintype "passive"))
      (node (ref "U3") (pin "1") (pinfunction "SW_1") (pintype "passive"))
    )
    (net (code "44") (name "Net-(U3-VOUT{slash}VFB)") (class "Default")
      (node (ref "R12") (pin "1") (pinfunction "1_1") (pintype "passive"))
      (node (ref "R9") (pin "2") (pinfunction "2_2") (pintype "passive"))
      (node (ref "U3") (pin "6") (pinfunction "VOUT/VFB_6") (pintype "input"))
    )
    (net (code "45") (name "Net-(U5-3D-FIX)") (class "Default")
      (node (ref "GPSLOCK") (pin "A") (pinfunction "A_A") (pintype "passive"))
      (node (ref "U5") (pin "P$5") (pinfunction "3D-FIX_P$5") (pintype "bidirectional"))
    )
    (net (code "46") (name "Net-(U5-VCC)") (class "Default")
      (node (ref "C15") (pin "1") (pinfunction "1_1") (pintype "passive"))
      (node (ref "L3") (pin "2") (pinfunction "2_2") (pintype "passive"))
      (node (ref "U5") (pin "P$1") (pinfunction "VCC_P$1") (pintype "bidirectional"))
    )
    (net (code "47") (name "Net-(U8-D)") (class "Default")
      (node (ref "C23") (pin "1") (pinfunction "1_1") (pintype "passive"))
      (node (ref "D3") (pin "C") (pinfunction "C_C") (pintype "passive"))
      (node (ref "U8") (pin "5") (pinfunction "D_5") (pintype "input"))
    )
    (net (code "48") (name "Net-(U8-FB)") (class "Default")
      (node (ref "C20") (pin "2") (pinfunction "2_2") (pintype "passive"))
      (node (ref "R17") (pin "2") (pinfunction "2_2") (pintype "passive"))
      (node (ref "U8") (pin "3") (pinfunction "FB_3") (pintype "input"))
    )
    (net (code "49") (name "Net-(U8-SW)") (class "Default")
      (node (ref "C23") (pin "2") (pinfunction "2_2") (pintype "passive"))
      (node (ref "L5") (pin "2") (pinfunction "2_2") (pintype "passive"))
      (node (ref "U8") (pin "1") (pinfunction "SW_1") (pintype "output"))
    )
    (net (code "50") (name "PTT") (class "Default")
      (node (ref "J1") (pin "D12") (pinfunction "D12_D12") (pintype "bidirectional"))
      (node (ref "U1") (pin "11") (pinfunction "A5_11") (pintype "input"))
    )
    (net (code "51") (name "unconnected-(BH2-+1-Pad+$2)") (class "Default")
      (node (ref "BH2") (pin "+$2") (pinfunction "+1_+$2") (pintype "passive"))
    )
    (net (code "52") (name "unconnected-(J1-*D3-PadD3)") (class "Default")
      (node (ref "J1") (pin "D3") (pinfunction "*D3_D3") (pintype "bidirectional"))
    )
    (net (code "53") (name "unconnected-(J1-PadA0)") (class "Default")
      (node (ref "J1") (pin "A0") (pinfunction "A0_A0") (pintype "bidirectional"))
    )
    (net (code "54") (name "unconnected-(J1-PadA1)") (class "Default")
      (node (ref "J1") (pin "A1") (pinfunction "A1_A1") (pintype "bidirectional"))
    )
    (net (code "55") (name "unconnected-(J1-PadA2)") (class "Default")
      (node (ref "J1") (pin "A2") (pinfunction "A2_A2") (pintype "bidirectional"))
    )
    (net (code "56") (name "unconnected-(J1-PadA3)") (class "Default")
      (node (ref "J1") (pin "A3") (pinfunction "A3_A3") (pintype "bidirectional"))
    )
    (net (code "57") (name "unconnected-(J1-PadA4)") (class "Default")
      (node (ref "J1") (pin "A4") (pinfunction "A4_A4") (pintype "bidirectional"))
    )
    (net (code "58") (name "unconnected-(J1-PadA5)") (class "Default")
      (node (ref "J1") (pin "A5") (pinfunction "A5_A5") (pintype "bidirectional"))
    )
    (net (code "59") (name "unconnected-(J1-PadAREF)") (class "Default")
      (node (ref "J1") (pin "AREF") (pinfunction "AREF_AREF") (pintype "bidirectional"))
    )
    (net (code "60") (name "unconnected-(J1-PadD2)") (class "Default")
      (node (ref "J1") (pin "D2") (pinfunction "D2_D2") (pintype "bidirectional"))
    )
    (net (code "61") (name "unconnected-(J1-PadIOREF)") (class "Default")
      (node (ref "J1") (pin "IOREF") (pinfunction "IOREF_IOREF") (pintype "bidirectional"))
    )
    (net (code "62") (name "unconnected-(JP3-Pad7)") (class "Default")
      (node (ref "JP3") (pin "7") (pinfunction "7_7") (pintype "passive"))
    )
    (net (code "63") (name "unconnected-(U3-HYST-Pad7)") (class "Default")
      (node (ref "U3") (pin "7") (pinfunction "HYST_7") (pintype "output"))
    )
    (net (code "64") (name "unconnected-(U5-GND-PadP$3)") (class "Default")
      (node (ref "U5") (pin "P$3") (pinfunction "GND_P$3") (pintype "bidirectional"))
    )
    (net (code "65") (name "unconnected-(U5-NC-PadP$6)") (class "Default")
      (node (ref "U5") (pin "P$6") (pinfunction "NC_P$6") (pintype "bidirectional"))
    )
    (net (code "66") (name "unconnected-(U5-NC-PadP$7)") (class "Default")
      (node (ref "U5") (pin "P$7") (pinfunction "NC_P$7") (pintype "bidirectional"))
    )
    (net (code "67") (name "unconnected-(U5-NC-PadP$15)") (class "Default")
      (node (ref "U5") (pin "P$15") (pinfunction "NC_P$15") (pintype "bidirectional"))
    )
    (net (code "68") (name "unconnected-(U5-NC-PadP$16)") (class "Default")
      (node (ref "U5") (pin "P$16") (pinfunction "NC_P$16") (pintype "bidirectional"))
    )
    (net (code "69") (name "unconnected-(U5-NC-PadP$17)") (class "Default")
      (node (ref "U5") (pin "P$17") (pinfunction "NC_P$17") (pintype "bidirectional"))
    )
    (net (code "70") (name "unconnected-(U5-NC-PadP$18)") (class "Default")
      (node (ref "U5") (pin "P$18") (pinfunction "NC_P$18") (pintype "bidirectional"))
    )
    (net (code "71") (name "unconnected-(U5-NC-PadP$20)") (class "Default")
      (node (ref "U5") (pin "P$20") (pinfunction "NC_P$20") (pintype "bidirectional"))
    )
    (net (code "72") (name "unconnected-(U5-NRESET-PadP$2)") (class "Default")
      (node (ref "U5") (pin "P$2") (pinfunction "NRESET_P$2") (pintype "bidirectional"))
    )
    (net (code "73") (name "unconnected-(U5-RTCM-PadP$14)") (class "Default")
      (node (ref "U5") (pin "P$14") (pinfunction "RTCM_P$14") (pintype "bidirectional"))
    )
  )
)
